# project_1.net
KiCad netlist of a schematic drawn in EAGLE
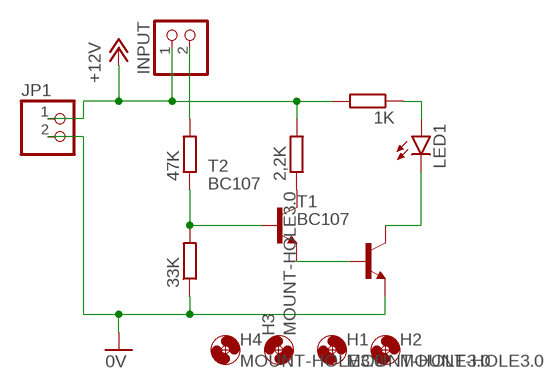
[diagram p0: schematic, sheet 1]

(export (version "E")
  (design (tool "Eeschema 10.0.6"))
  (components
    (comp (ref "1K")
      (value "R-EU_0207/12")
      (footprint "eagle-import:0207_12")
      (libsource (lib "eagle-import") (part "R-EU_0207/12"))
    )
    (comp (ref "2,2K")
      (value "R-EU_0207/15")
      (footprint "eagle-import:0207_15")
      (libsource (lib "eagle-import") (part "R-EU_0207/15"))
    )
    (comp (ref "33K")
      (value "R-EU_0207/15")
      (footprint "eagle-import:0207_15")
      (libsource (lib "eagle-import") (part "R-EU_0207/15"))
    )
    (comp (ref "47K")
      (value "R-EU_0207/15")
      (footprint "eagle-import:0207_15")
      (libsource (lib "eagle-import") (part "R-EU_0207/15"))
    )
    (comp (ref "H1")
      (value "MOUNT-HOLE3.0")
      (footprint "eagle-import:3,0")
      (libsource (lib "eagle-import") (part "MOUNT-HOLE3.0"))
    )
    (comp (ref "H2")
      (value "MOUNT-HOLE3.0")
      (footprint "eagle-import:3,0")
      (libsource (lib "eagle-import") (part "MOUNT-HOLE3.0"))
    )
    (comp (ref "H3")
      (value "MOUNT-HOLE3.0")
      (footprint "eagle-import:3,0")
      (libsource (lib "eagle-import") (part "MOUNT-HOLE3.0"))
    )
    (comp (ref "H4")
      (value "MOUNT-HOLE3.0")
      (footprint "eagle-import:3,0")
      (libsource (lib "eagle-import") (part "MOUNT-HOLE3.0"))
    )
    (comp (ref "INPUT")
      (value "PINHD-1X2")
      (footprint "eagle-import:1X02")
      (libsource (lib "eagle-import") (part "PINHD-1X2"))
    )
    (comp (ref "JP1")
      (value "PINHD-1X2")
      (footprint "eagle-import:1X02")
      (libsource (lib "eagle-import") (part "PINHD-1X2"))
    )
    (comp (ref "LED1")
      (value "LED5MM")
      (footprint "eagle-import:LED5MM")
      (libsource (lib "eagle-import") (part "LED5MM"))
    )
    (comp (ref "T1")
      (value "BC107")
      (footprint "eagle-import:TO18")
      (libsource (lib "eagle-import") (part "BC107"))
    )
    (comp (ref "T2")
      (value "BC107")
      (footprint "eagle-import:TO18")
      (libsource (lib "eagle-import") (part "BC107"))
    )
  )
  (nets
    (net (code "1") (name "+12V") (class "Default")
      (node (ref "1K") (pin "2") (pinfunction "2_2") (pintype "passive"))
      (node (ref "2,2K") (pin "2") (pinfunction "2_2") (pintype "passive"))
      (node (ref "INPUT") (pin "1") (pinfunction "1_1") (pintype "passive"))
      (node (ref "JP1") (pin "1") (pinfunction "1_1") (pintype "passive"))
    )
    (net (code "2") (name "0V") (class "Default")
      (node (ref "33K") (pin "1") (pinfunction "1_1") (pintype "passive"))
      (node (ref "JP1") (pin "2") (pinfunction "2_2") (pintype "passive"))
      (node (ref "T1") (pin "1") (pinfunction "E_1") (pintype "passive"))
    )
    (net (code "3") (name "Net-(1K-Pad1)") (class "Default")
      (node (ref "1K") (pin "1") (pinfunction "1_1") (pintype "passive"))
      (node (ref "LED1") (pin "A") (pinfunction "A_A") (pintype "passive"))
    )
    (net (code "4") (name "Net-(47K-Pad2)") (class "Default")
      (node (ref "47K") (pin "2") (pinfunction "2_2") (pintype "passive"))
      (node (ref "INPUT") (pin "2") (pinfunction "2_2") (pintype "passive"))
    )
    (net (code "5") (name "Net-(LED1-C)") (class "Default")
      (node (ref "LED1") (pin "K") (pinfunction "C_K") (pintype "passive"))
      (node (ref "T1") (pin "3") (pinfunction "C_3") (pintype "passive"))
    )
    (net (code "6") (name "Net-(T1-B)") (class "Default")
      (node (ref "T1") (pin "2") (pinfunction "B_2") (pintype "passive"))
      (node (ref "T2") (pin "1") (pinfunction "E_1") (pintype "passive"))
    )
    (net (code "7") (name "Net-(T2-B)") (class "Default")
      (node (ref "33K") (pin "2") (pinfunction "2_2") (pintype "passive"))
      (node (ref "47K") (pin "1") (pinfunction "1_1") (pintype "passive"))
      (node (ref "T2") (pin "2") (pinfunction "B_2") (pintype "passive"))
    )
    (net (code "8") (name "Net-(T2-C)") (class "Default")
      (node (ref "2,2K") (pin "1") (pinfunction "1_1") (pintype "passive"))
      (node (ref "T2") (pin "3") (pinfunction "C_3") (pintype "passive"))
    )
  )
)
